# EPS_MPPT_XY_Interface.net
KiCad netlist of a schematic drawn in Altium Designer
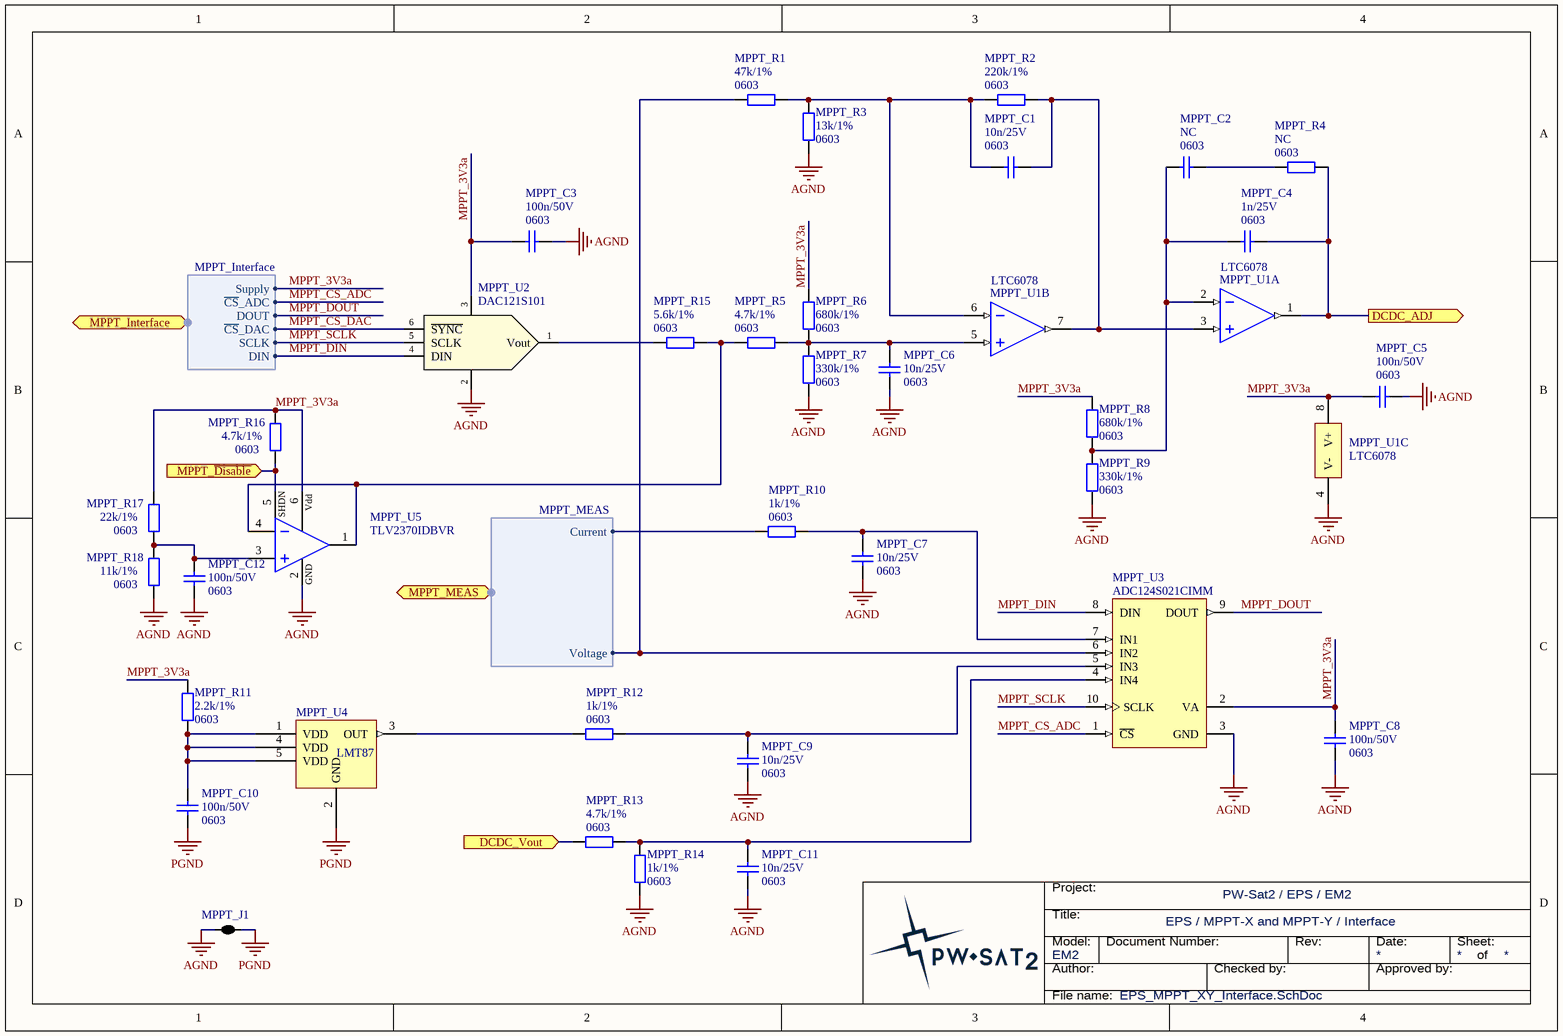
[diagram p0: EPS_MPPT_XY_Interface.SchDoc]

(export (version "E")
  (design (tool "Eeschema 10.0.6"))
  (components
    (comp (ref "MPPT_C1")
      (value "10n/25V")
      (footprint "SMD_Capacitor_0603")
      (description "Cap")
      (fields (field (name "PACKAGE") "0603"))
      (libsource (lib "capacitors") (part "Cap"))
    )
    (comp (ref "MPPT_C2")
      (value "NC")
      (footprint "SMD_Capacitor_0603")
      (description "Cap")
      (fields (field (name "PACKAGE") "0603"))
      (libsource (lib "capacitors") (part "Cap"))
    )
    (comp (ref "MPPT_C3")
      (value "100n/50V")
      (footprint "SMD_Capacitor_0603")
      (description "Ceramic Cap Kemet COTS 100n/50V X7R 0603")
      (fields
        (field (name "MANUFACTURER") "Kemet")
        (field (name "MANUFACTURERPARTNUMBER") "C0603T104K5RALTU")
        (field (name "PACKAGE") "0603")
      )
      (libsource (lib "capacitors") (part "Cer_C0603T104K5RALTU"))
    )
    (comp (ref "MPPT_C4")
      (value "1n/25V")
      (footprint "SMD_Capacitor_0603")
      (description "Cap")
      (fields (field (name "PACKAGE") "0603"))
      (libsource (lib "capacitors") (part "Cap"))
    )
    (comp (ref "MPPT_C5")
      (value "100n/50V")
      (footprint "SMD_Capacitor_0603")
      (description "Ceramic Cap Kemet COTS 100n/50V X7R 0603")
      (fields
        (field (name "MANUFACTURER") "Kemet")
        (field (name "MANUFACTURERPARTNUMBER") "C0603T104K5RALTU")
        (field (name "PACKAGE") "0603")
      )
      (libsource (lib "capacitors") (part "Cer_C0603T104K5RALTU"))
    )
    (comp (ref "MPPT_C6")
      (value "10n/25V")
      (footprint "SMD_Capacitor_0603")
      (description "Cap")
      (fields (field (name "PACKAGE") "0603"))
      (libsource (lib "capacitors") (part "Cap"))
    )
    (comp (ref "MPPT_C7")
      (value "10n/25V")
      (footprint "SMD_Capacitor_0603")
      (description "Cap")
      (fields (field (name "PACKAGE") "0603"))
      (libsource (lib "capacitors") (part "Cap"))
    )
    (comp (ref "MPPT_C8")
      (value "100n/50V")
      (footprint "SMD_Capacitor_0603")
      (description "Ceramic Cap Kemet COTS 100n/50V X7R 0603")
      (fields
        (field (name "MANUFACTURER") "Kemet")
        (field (name "MANUFACTURERPARTNUMBER") "C0603T104K5RALTU")
        (field (name "PACKAGE") "0603")
      )
      (libsource (lib "capacitors") (part "Cer_C0603T104K5RALTU"))
    )
    (comp (ref "MPPT_C9")
      (value "10n/25V")
      (footprint "SMD_Capacitor_0603")
      (description "Cap")
      (fields (field (name "PACKAGE") "0603"))
      (libsource (lib "capacitors") (part "Cap"))
    )
    (comp (ref "MPPT_C10")
      (value "100n/50V")
      (footprint "SMD_Capacitor_0603")
      (description "Ceramic Cap Kemet COTS 100n/50V X7R 0603")
      (fields
        (field (name "MANUFACTURER") "Kemet")
        (field (name "MANUFACTURERPARTNUMBER") "C0603T104K5RALTU")
        (field (name "PACKAGE") "0603")
      )
      (libsource (lib "capacitors") (part "Cer_C0603T104K5RALTU"))
    )
    (comp (ref "MPPT_C11")
      (value "10n/25V")
      (footprint "SMD_Capacitor_0603")
      (description "Cap")
      (fields (field (name "PACKAGE") "0603"))
      (libsource (lib "capacitors") (part "Cap"))
    )
    (comp (ref "MPPT_C12")
      (value "100n/50V")
      (footprint "SMD_Capacitor_0603")
      (description "Cap")
      (fields (field (name "PACKAGE") "0603"))
      (libsource (lib "capacitors") (part "Cap"))
    )
    (comp (ref "MPPT_J1")
      (value "2 way net tie junction")
      (footprint "2way_LP")
      (libsource (lib "NetTieLib") (part "2way"))
    )
    (comp (ref "MPPT_R1")
      (value "47k/1%")
      (footprint "SMD_Resistor_0603")
      (fields (field (name "PACKAGE") "0603"))
      (libsource (lib "resistors") (part "Res"))
    )
    (comp (ref "MPPT_R2")
      (value "220k/1%")
      (footprint "SMD_Resistor_0603")
      (fields (field (name "PACKAGE") "0603"))
      (libsource (lib "resistors") (part "Res"))
    )
    (comp (ref "MPPT_R3")
      (value "13k/1%")
      (footprint "SMD_Resistor_0603")
      (fields (field (name "PACKAGE") "0603"))
      (libsource (lib "") (part "Res_2"))
    )
    (comp (ref "MPPT_R4")
      (value "NC")
      (footprint "SMD_Resistor_0603")
      (fields (field (name "PACKAGE") "0603"))
      (libsource (lib "resistors") (part "Res"))
    )
    (comp (ref "MPPT_R5")
      (value "4.7k/1%")
      (footprint "SMD_Resistor_0603")
      (fields (field (name "PACKAGE") "0603"))
      (libsource (lib "resistors") (part "Res"))
    )
    (comp (ref "MPPT_R6")
      (value "680k/1%")
      (footprint "SMD_Resistor_0603")
      (fields (field (name "PACKAGE") "0603"))
      (libsource (lib "") (part "Res_2"))
    )
    (comp (ref "MPPT_R7")
      (value "330k/1%")
      (footprint "SMD_Resistor_0603")
      (fields (field (name "PACKAGE") "0603"))
      (libsource (lib "") (part "Res_2"))
    )
    (comp (ref "MPPT_R8")
      (value "680k/1%")
      (footprint "SMD_Resistor_0603")
      (fields (field (name "PACKAGE") "0603"))
      (libsource (lib "") (part "Res_2"))
    )
    (comp (ref "MPPT_R9")
      (value "330k/1%")
      (footprint "SMD_Resistor_0603")
      (fields (field (name "PACKAGE") "0603"))
      (libsource (lib "") (part "Res_2"))
    )
    (comp (ref "MPPT_R10")
      (value "1k/1%")
      (footprint "SMD_Resistor_0603")
      (fields (field (name "PACKAGE") "0603"))
      (libsource (lib "resistors") (part "Res"))
    )
    (comp (ref "MPPT_R11")
      (value "2.2k/1%")
      (footprint "SMD_Resistor_0603")
      (fields (field (name "PACKAGE") "0603"))
      (libsource (lib "") (part "Res_1"))
    )
    (comp (ref "MPPT_R12")
      (value "1k/1%")
      (footprint "SMD_Resistor_0603")
      (fields (field (name "PACKAGE") "0603"))
      (libsource (lib "resistors") (part "Res"))
    )
    (comp (ref "MPPT_R13")
      (value "4.7k/1%")
      (footprint "SMD_Resistor_0603")
      (fields (field (name "PACKAGE") "0603"))
      (libsource (lib "resistors") (part "Res"))
    )
    (comp (ref "MPPT_R14")
      (value "1k/1%")
      (footprint "SMD_Resistor_0603")
      (fields (field (name "PACKAGE") "0603"))
      (libsource (lib "") (part "Res_2"))
    )
    (comp (ref "MPPT_R15")
      (value "5.6k/1%")
      (footprint "SMD_Resistor_0603")
      (fields (field (name "PACKAGE") "0603"))
      (libsource (lib "resistors") (part "Res"))
    )
    (comp (ref "MPPT_R16")
      (value "4.7k/1%")
      (footprint "SMD_Resistor_0603")
      (description "4.7k/1% Vishay CRCW 0603 Resistor. 100mW, 100ppm, 75V.")
      (fields
        (field (name "MANUFACTURER") "Vishay")
        (field (name "MANUFACTUERPARTNUMBER") "CRCW06034K70FKxxxx")
        (field (name "PACKAGE") "0603")
      )
      (libsource (lib "resistors") (part "CRCW06034K70FKxxxx"))
    )
    (comp (ref "MPPT_R17")
      (value "22k/1%")
      (footprint "SMD_Resistor_0603")
      (description "4.7k/1% Vishay CRCW 0603 Resistor. 100mW, 100ppm, 75V.")
      (fields
        (field (name "MANUFACTURER") "Vishay")
        (field (name "MANUFACTUERPARTNUMBER") "CRCW06034K70FKxxxx")
        (field (name "PACKAGE") "0603")
      )
      (libsource (lib "resistors") (part "CRCW06034K70FKxxxx"))
    )
    (comp (ref "MPPT_R18")
      (value "11k/1%")
      (footprint "SMD_Resistor_0603")
      (description "4.7k/1% Vishay CRCW 0603 Resistor. 100mW, 100ppm, 75V.")
      (fields
        (field (name "MANUFACTURER") "Vishay")
        (field (name "MANUFACTUERPARTNUMBER") "CRCW06034K70FKxxxx")
        (field (name "PACKAGE") "0603")
      )
      (libsource (lib "resistors") (part "CRCW06034K70FKxxxx"))
    )
    (comp (ref "MPPT_U1")
      (value "LTC6078")
      (footprint "MSOP-8")
      (description "Rail-to-rail, quad operational amplifier. Library compatible with LTC608X LTC607X op-amps")
      (fields (field (name "MANUFACTURER") "Linear Technology"))
      (libsource (lib "microcircuits") (part "LTC6078"))
    )
    (comp (ref "MPPT_U2")
      (value "DAC121S101")
      (footprint "SOT23-6")
      (description "12-Bit Micro Power, RRO Digital-to-Analog Converter.")
      (fields (field (name "MANUFACTURER") "Texas Instruments"))
      (libsource (lib "microcircuits") (part "DAC121S101"))
    )
    (comp (ref "MPPT_U3")
      (value "ADC124S021CIMM")
      (footprint "MUB10A_L")
      (fields
        (field (name "MANUFACTURER") "Texas Instruments")
        (field (name "MANUFACTURERPARTNUMBER") "ADC124S021CIMM/NOPB")
      )
      (libsource (lib "microcircuits") (part "ADC124S021CIMM/NOPB"))
    )
    (comp (ref "MPPT_U4")
      (value "LMT87")
      (footprint "SC70-LT5_N")
      (description "Analog Temperature Sensors with Class-AB Output")
      (libsource (lib "microcircuits") (part "LMT87"))
    )
    (comp (ref "MPPT_U5")
      (value "~")
      (footprint "SOT23-6")
      (description "3-MHz Rail-to-Rail In/Out Single Operational Amplifier")
      (fields
        (field (name "MANUFACTURER") "Texas Instruments")
        (field (name "MANUFACTURERPARTNUMBER") "TLV2370IDBVR")
      )
      (libsource (lib "microcircuits") (part "TLV2370IDBVR"))
    )
  )
  (nets
    (net (code "3") (name "/Current") (class "Default")
      (node (ref "MPPT_R10") (pin "2") (pinfunction "2_2") (pintype "passive"))
    )
    (net (code "4") (name "/DCDC_ADJ") (class "Default")
      (node (ref "MPPT_C4") (pin "2") (pinfunction "2_2") (pintype "passive"))
      (node (ref "MPPT_R4") (pin "1") (pinfunction "1_1") (pintype "passive"))
      (node (ref "MPPT_U1") (pin "1") (pinfunction "OUT_A_1") (pintype "output"))
    )
    (net (code "5") (name "/DCDC_Vout") (class "Default")
      (node (ref "MPPT_R13") (pin "2") (pinfunction "2_2") (pintype "passive"))
    )
    (net (code "6") (name "/MPPT_3V3a") (class "Default")
      (node (ref "MPPT_C3") (pin "2") (pinfunction "2_2") (pintype "passive"))
      (node (ref "MPPT_C5") (pin "1") (pinfunction "1_1") (pintype "passive"))
      (node (ref "MPPT_C8") (pin "1") (pinfunction "1_1") (pintype "passive"))
      (node (ref "MPPT_R11") (pin "1") (pinfunction "1_1") (pintype "passive"))
      (node (ref "MPPT_R16") (pin "1") (pinfunction "1_1") (pintype "passive"))
      (node (ref "MPPT_R17") (pin "1") (pinfunction "1_1") (pintype "passive"))
      (node (ref "MPPT_R6") (pin "2") (pinfunction "2_2") (pintype "passive"))
      (node (ref "MPPT_R8") (pin "2") (pinfunction "2_2") (pintype "passive"))
      (node (ref "MPPT_U1") (pin "8") (pinfunction "V+_8") (pintype "power_in"))
      (node (ref "MPPT_U2") (pin "3") (pinfunction "Va_3") (pintype "passive"))
      (node (ref "MPPT_U3") (pin "2") (pinfunction "VA_2") (pintype "power_in"))
      (node (ref "MPPT_U5") (pin "6") (pinfunction "Vdd_6") (pintype "passive"))
    )
    (net (code "7") (name "/MPPT_CS_ADC") (class "Default")
      (node (ref "MPPT_U3") (pin "1") (pinfunction "~{CS}_1") (pintype "input"))
    )
    (net (code "8") (name "/MPPT_CS_DAC") (class "Default")
      (node (ref "MPPT_U2") (pin "6") (pinfunction "~{SYNC}_6") (pintype "passive"))
    )
    (net (code "9") (name "/MPPT_DIN") (class "Default")
      (node (ref "MPPT_U2") (pin "4") (pinfunction "DIN_4") (pintype "passive"))
      (node (ref "MPPT_U3") (pin "8") (pinfunction "DIN_8") (pintype "input"))
    )
    (net (code "10") (name "/MPPT_DOUT") (class "Default")
      (node (ref "MPPT_U3") (pin "9") (pinfunction "DOUT_9") (pintype "output"))
    )
    (net (code "11") (name "/MPPT_SCLK") (class "Default")
      (node (ref "MPPT_U2") (pin "5") (pinfunction "SCLK_5") (pintype "passive"))
      (node (ref "MPPT_U3") (pin "10") (pinfunction "SCLK_10") (pintype "input"))
    )
    (net (code "12") (name "/MPPT_~{Disable}") (class "Default")
      (node (ref "MPPT_R16") (pin "2") (pinfunction "2_2") (pintype "passive"))
      (node (ref "MPPT_U5") (pin "5") (pinfunction "SHDN_5") (pintype "passive"))
    )
    (net (code "13") (name "/Voltage") (class "Default")
      (node (ref "MPPT_R1") (pin "2") (pinfunction "2_2") (pintype "passive"))
      (node (ref "MPPT_U3") (pin "6") (pinfunction "IN2_6") (pintype "input"))
    )
    (net (code "16") (name "AGND") (class "Default")
      (node (ref "MPPT_C11") (pin "1") (pinfunction "1_1") (pintype "passive"))
      (node (ref "MPPT_C12") (pin "1") (pinfunction "1_1") (pintype "passive"))
      (node (ref "MPPT_C3") (pin "1") (pinfunction "1_1") (pintype "passive"))
      (node (ref "MPPT_C5") (pin "2") (pinfunction "2_2") (pintype "passive"))
      (node (ref "MPPT_C6") (pin "1") (pinfunction "1_1") (pintype "passive"))
      (node (ref "MPPT_C7") (pin "1") (pinfunction "1_1") (pintype "passive"))
      (node (ref "MPPT_C8") (pin "2") (pinfunction "2_2") (pintype "passive"))
      (node (ref "MPPT_C9") (pin "1") (pinfunction "1_1") (pintype "passive"))
      (node (ref "MPPT_J1") (pin "2") (pinfunction "2_2") (pintype "passive"))
      (node (ref "MPPT_R14") (pin "1") (pinfunction "1_1") (pintype "passive"))
      (node (ref "MPPT_R18") (pin "2") (pinfunction "2_2") (pintype "passive"))
      (node (ref "MPPT_R3") (pin "1") (pinfunction "1_1") (pintype "passive"))
      (node (ref "MPPT_R7") (pin "1") (pinfunction "1_1") (pintype "passive"))
      (node (ref "MPPT_R9") (pin "1") (pinfunction "1_1") (pintype "passive"))
      (node (ref "MPPT_U1") (pin "4") (pinfunction "V-_4") (pintype "power_in"))
      (node (ref "MPPT_U2") (pin "2") (pinfunction "GND_2") (pintype "passive"))
      (node (ref "MPPT_U3") (pin "3") (pinfunction "GND_3") (pintype "power_in"))
      (node (ref "MPPT_U5") (pin "2") (pinfunction "GND_2") (pintype "passive"))
    )
    (net (code "17") (name "Net-(MPPT_C2-Pad2)") (class "Default")
      (node (ref "MPPT_C2") (pin "2") (pinfunction "2_2") (pintype "passive"))
      (node (ref "MPPT_R4") (pin "2") (pinfunction "2_2") (pintype "passive"))
    )
    (net (code "18") (name "Net-(MPPT_C10-Pad1)") (class "Default")
      (node (ref "MPPT_C10") (pin "1") (pinfunction "1_1") (pintype "passive"))
      (node (ref "MPPT_R11") (pin "2") (pinfunction "2_2") (pintype "passive"))
      (node (ref "MPPT_U4") (pin "1") (pinfunction "VDD_1") (pintype "passive"))
      (node (ref "MPPT_U4") (pin "4") (pinfunction "VDD_4") (pintype "power_in"))
      (node (ref "MPPT_U4") (pin "5") (pinfunction "VDD_5") (pintype "power_in"))
    )
    (net (code "19") (name "Net-(MPPT_U1A-IN+_A)") (class "Default")
      (node (ref "MPPT_C1") (pin "2") (pinfunction "2_2") (pintype "passive"))
      (node (ref "MPPT_R2") (pin "1") (pinfunction "1_1") (pintype "passive"))
      (node (ref "MPPT_U1") (pin "3") (pinfunction "IN+_A_3") (pintype "input"))
      (node (ref "MPPT_U1") (pin "7") (pinfunction "OUT_B_7") (pintype "output"))
    )
    (net (code "20") (name "Net-(MPPT_U1A-IN-_A)") (class "Default")
      (node (ref "MPPT_C2") (pin "1") (pinfunction "1_1") (pintype "passive"))
      (node (ref "MPPT_C4") (pin "1") (pinfunction "1_1") (pintype "passive"))
      (node (ref "MPPT_R8") (pin "1") (pinfunction "1_1") (pintype "passive"))
      (node (ref "MPPT_R9") (pin "2") (pinfunction "2_2") (pintype "passive"))
      (node (ref "MPPT_U1") (pin "2") (pinfunction "IN-_A_2") (pintype "input"))
    )
    (net (code "21") (name "Net-(MPPT_U1B-IN+_B)") (class "Default")
      (node (ref "MPPT_C6") (pin "2") (pinfunction "2_2") (pintype "passive"))
      (node (ref "MPPT_R5") (pin "1") (pinfunction "1_1") (pintype "passive"))
      (node (ref "MPPT_R6") (pin "1") (pinfunction "1_1") (pintype "passive"))
      (node (ref "MPPT_R7") (pin "2") (pinfunction "2_2") (pintype "passive"))
      (node (ref "MPPT_U1") (pin "5") (pinfunction "IN+_B_5") (pintype "input"))
    )
    (net (code "22") (name "Net-(MPPT_U1B-IN-_B)") (class "Default")
      (node (ref "MPPT_C1") (pin "1") (pinfunction "1_1") (pintype "passive"))
      (node (ref "MPPT_R1") (pin "1") (pinfunction "1_1") (pintype "passive"))
      (node (ref "MPPT_R2") (pin "2") (pinfunction "2_2") (pintype "passive"))
      (node (ref "MPPT_R3") (pin "2") (pinfunction "2_2") (pintype "passive"))
      (node (ref "MPPT_U1") (pin "6") (pinfunction "IN-_B_6") (pintype "input"))
    )
    (net (code "23") (name "Net-(MPPT_U2-Vout)") (class "Default")
      (node (ref "MPPT_R15") (pin "2") (pinfunction "2_2") (pintype "passive"))
      (node (ref "MPPT_U2") (pin "1") (pinfunction "Vout_1") (pintype "passive"))
    )
    (net (code "24") (name "Net-(MPPT_U3-IN1)") (class "Default")
      (node (ref "MPPT_C7") (pin "2") (pinfunction "2_2") (pintype "passive"))
      (node (ref "MPPT_R10") (pin "1") (pinfunction "1_1") (pintype "passive"))
      (node (ref "MPPT_U3") (pin "7") (pinfunction "IN1_7") (pintype "input"))
    )
    (net (code "25") (name "Net-(MPPT_U3-IN3)") (class "Default")
      (node (ref "MPPT_C9") (pin "2") (pinfunction "2_2") (pintype "passive"))
      (node (ref "MPPT_R12") (pin "1") (pinfunction "1_1") (pintype "passive"))
      (node (ref "MPPT_U3") (pin "5") (pinfunction "IN3_5") (pintype "input"))
    )
    (net (code "26") (name "Net-(MPPT_U3-IN4)") (class "Default")
      (node (ref "MPPT_C11") (pin "2") (pinfunction "2_2") (pintype "passive"))
      (node (ref "MPPT_R13") (pin "1") (pinfunction "1_1") (pintype "passive"))
      (node (ref "MPPT_R14") (pin "2") (pinfunction "2_2") (pintype "passive"))
      (node (ref "MPPT_U3") (pin "4") (pinfunction "IN4_4") (pintype "input"))
    )
    (net (code "27") (name "Net-(MPPT_U4-OUT)") (class "Default")
      (node (ref "MPPT_R12") (pin "2") (pinfunction "2_2") (pintype "passive"))
      (node (ref "MPPT_U4") (pin "3") (pinfunction "OUT_3") (pintype "output"))
    )
    (net (code "28") (name "Net-(MPPT_U5-IN+)") (class "Default")
      (node (ref "MPPT_C12") (pin "2") (pinfunction "2_2") (pintype "passive"))
      (node (ref "MPPT_R17") (pin "2") (pinfunction "2_2") (pintype "passive"))
      (node (ref "MPPT_R18") (pin "1") (pinfunction "1_1") (pintype "passive"))
      (node (ref "MPPT_U5") (pin "3") (pinfunction "IN+_3") (pintype "passive"))
    )
    (net (code "29") (name "Net-(MPPT_U5-IN-)") (class "Default")
      (node (ref "MPPT_R15") (pin "1") (pinfunction "1_1") (pintype "passive"))
      (node (ref "MPPT_R5") (pin "2") (pinfunction "2_2") (pintype "passive"))
      (node (ref "MPPT_U5") (pin "1") (pinfunction "OUT_1") (pintype "passive"))
      (node (ref "MPPT_U5") (pin "4") (pinfunction "IN-_4") (pintype "passive"))
    )
    (net (code "30") (name "PGND") (class "Default")
      (node (ref "MPPT_C10") (pin "2") (pinfunction "2_2") (pintype "passive"))
      (node (ref "MPPT_J1") (pin "1") (pinfunction "1_1") (pintype "passive"))
      (node (ref "MPPT_U4") (pin "2") (pinfunction "GND_2") (pintype "power_in"))
    )
  )
)
